# cnc3018_ctrl.net
KiCad netlist of a schematic drawn in EasyEDA
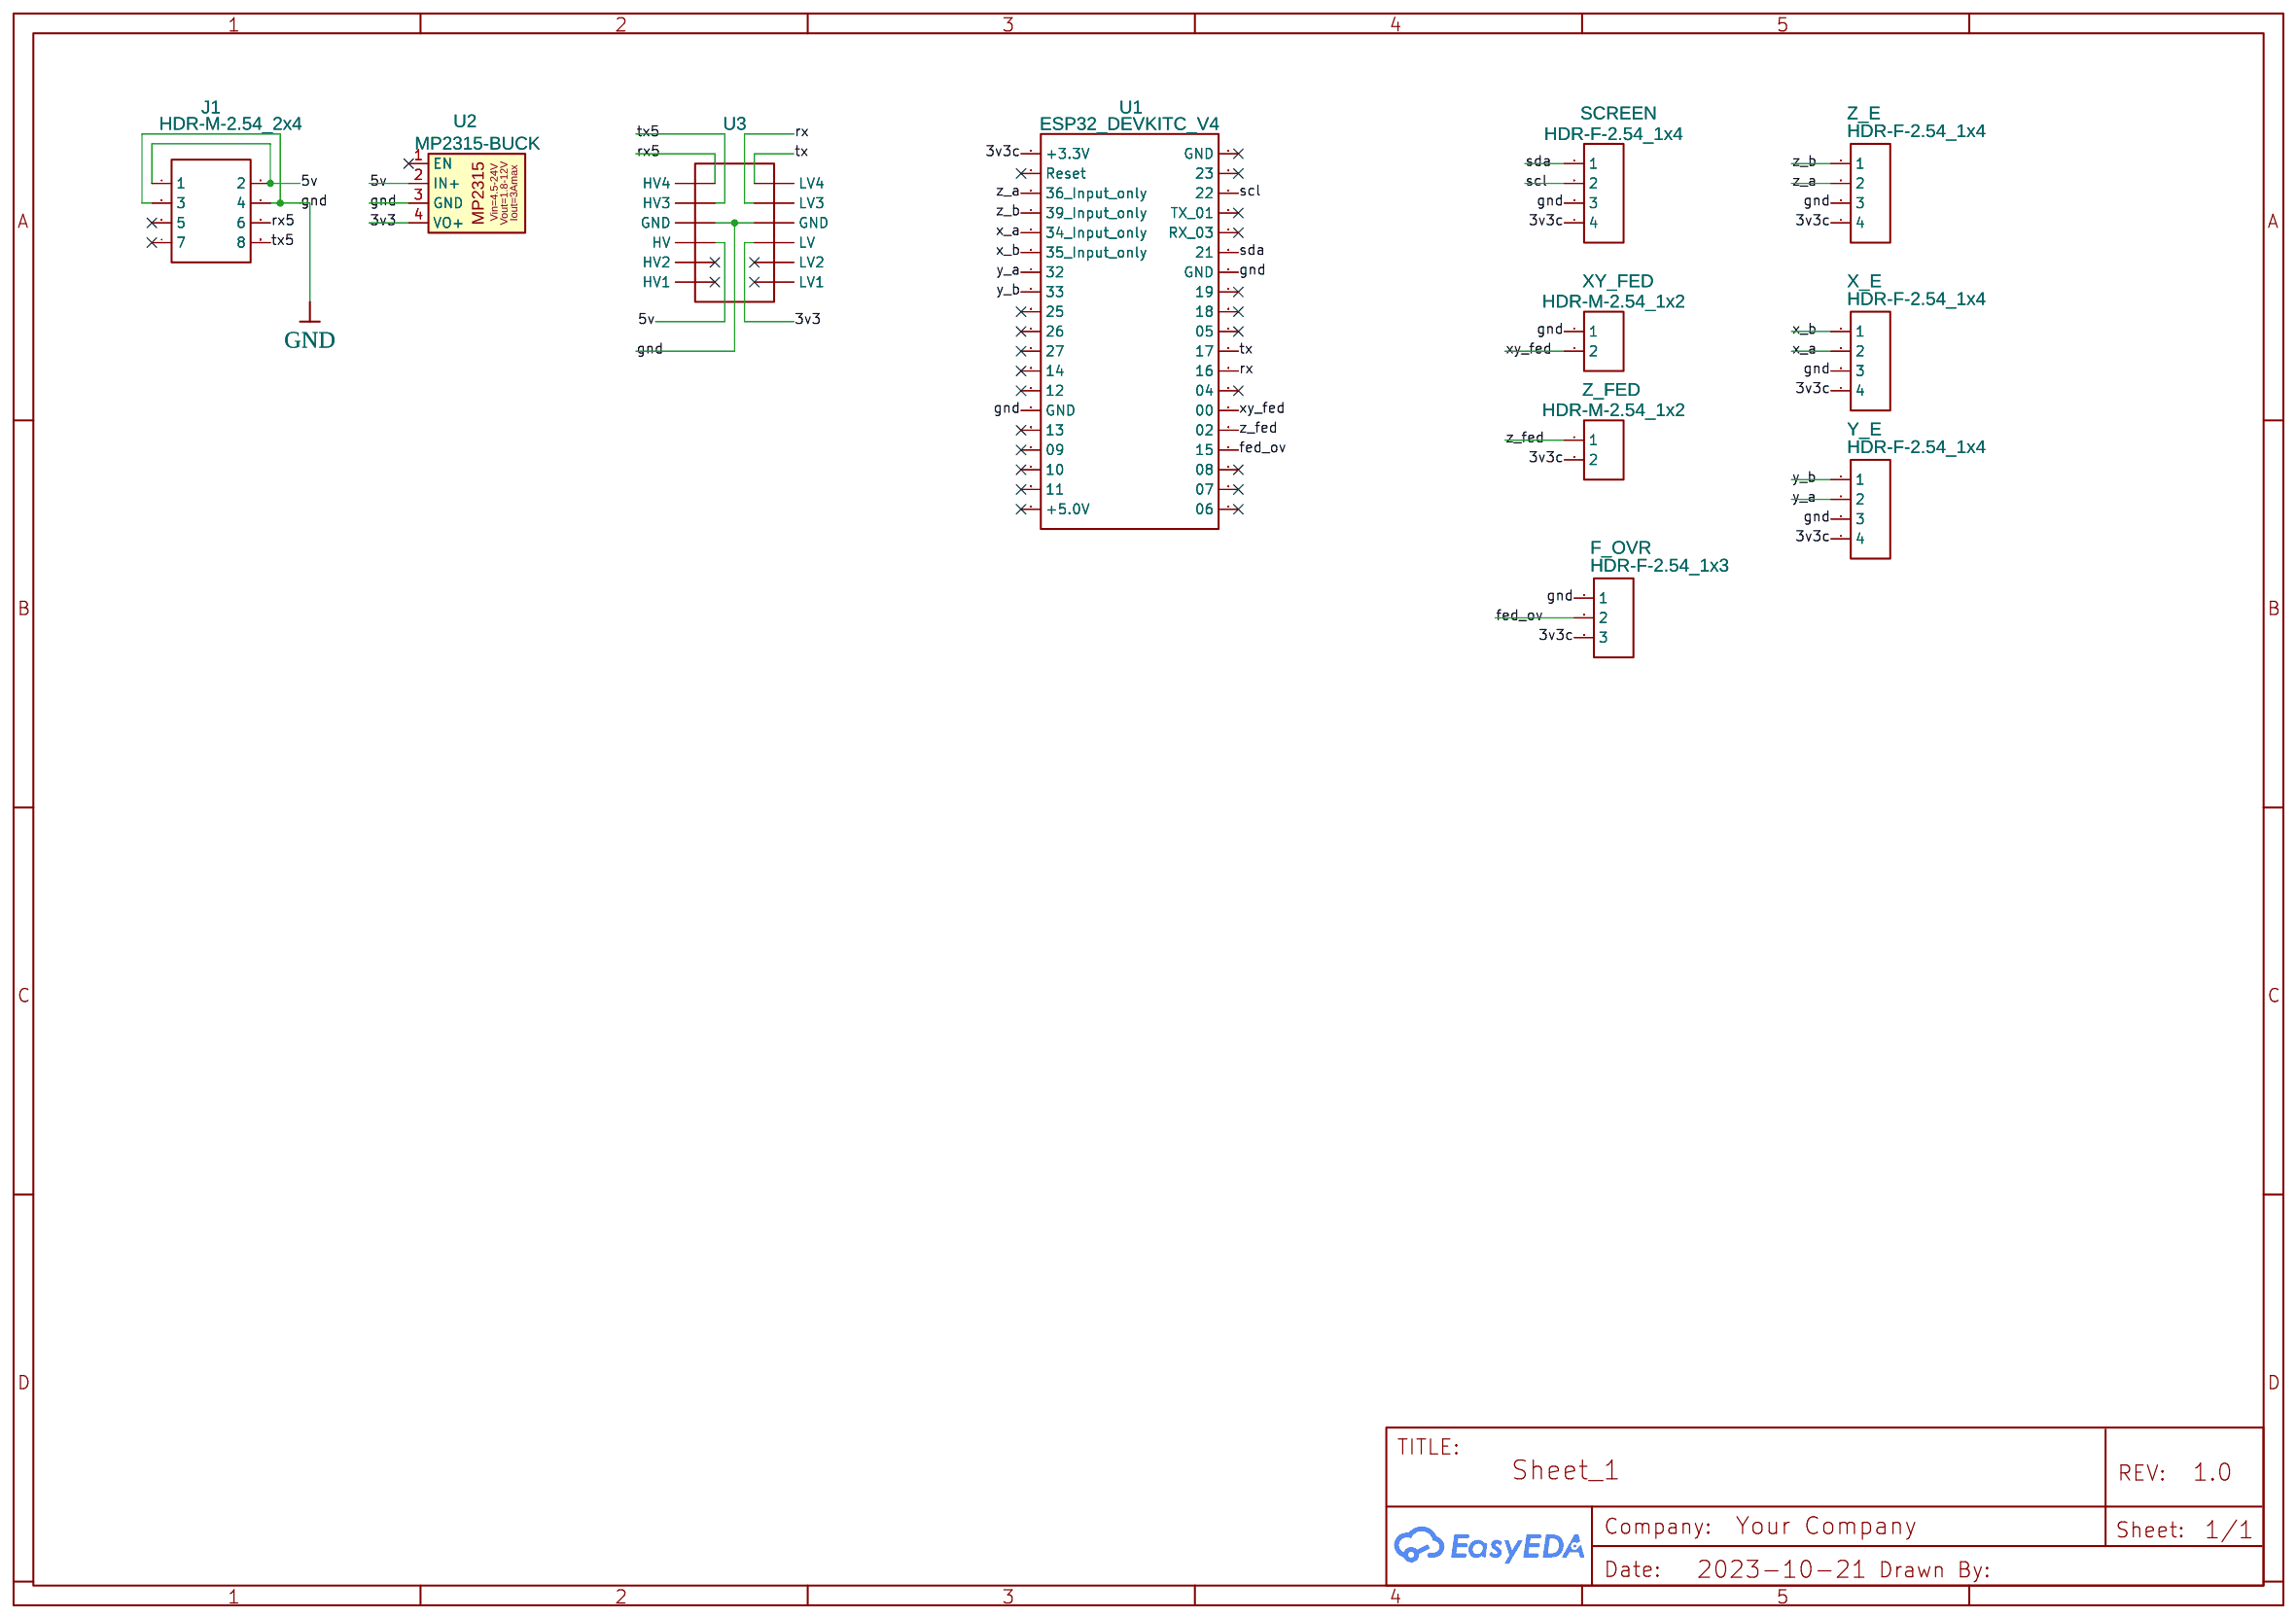
[diagram p0: schematic sheet]

(export (version "E")
  (design (tool "Eeschema 10.0.6"))
  (components
    (comp (ref "F_OVR") (value "HDR-F-2.54_1x3") (libsource (lib "") (part "HDR-F-2.54_1x3")))
    (comp (ref "J1") (value "HDR-M-2.54_2x4") (libsource (lib "") (part "HDR-M-2.54_2x4")))
    (comp (ref "SCREEN") (value "HDR-F-2.54_1x4") (libsource (lib "") (part "HDR-F-2.54_1x4")))
    (comp (ref "U1") (value "ESP32_DEVKITC_V4") (libsource (lib "") (part "ESP32_DEVKITC_V4")))
    (comp (ref "U2") (value "MP2315-BUCK") (libsource (lib "") (part "MP2315-BUCK")))
    (comp (ref "U3") (value "NO") (libsource (lib "") (part "LEVEL-CONVERTER")))
    (comp (ref "XY_FED") (value "HDR-M-2.54_1x2") (libsource (lib "") (part "HDR-M-2.54_1x2_1")))
    (comp (ref "X_E") (value "HDR-F-2.54_1x4") (libsource (lib "") (part "HDR-F-2.54_1x4_1")))
    (comp (ref "Y_E") (value "HDR-F-2.54_1x4") (libsource (lib "") (part "HDR-F-2.54_1x4_3")))
    (comp (ref "Z_E") (value "HDR-F-2.54_1x4") (libsource (lib "") (part "HDR-F-2.54_1x4_2")))
    (comp (ref "Z_FED") (value "HDR-M-2.54_1x2") (libsource (lib "") (part "HDR-M-2.54_1x2")))
  )
  (nets
    (net (code "1") (name "/3v3") (class "Default")
      (node (ref "U2") (pin "4") (pinfunction "VO+_4") (pintype "unspecified"))
      (node (ref "U3") (pin "3") (pinfunction "LV_3") (pintype "unspecified"))
    )
    (net (code "2") (name "/3v3c") (class "Default")
      (node (ref "F_OVR") (pin "3") (pinfunction "3_3") (pintype "input"))
      (node (ref "SCREEN") (pin "4") (pinfunction "4_4") (pintype "unspecified"))
      (node (ref "U1") (pin "1") (pinfunction "+3.3V_1") (pintype "unspecified"))
      (node (ref "X_E") (pin "4") (pinfunction "4_4") (pintype "unspecified"))
      (node (ref "Y_E") (pin "4") (pinfunction "4_4") (pintype "unspecified"))
      (node (ref "Z_E") (pin "4") (pinfunction "4_4") (pintype "unspecified"))
      (node (ref "Z_FED") (pin "2") (pinfunction "2_2") (pintype "unspecified"))
    )
    (net (code "3") (name "/5v") (class "Default")
      (node (ref "J1") (pin "1") (pinfunction "1_1") (pintype "unspecified"))
      (node (ref "J1") (pin "2") (pinfunction "2_2") (pintype "unspecified"))
      (node (ref "U2") (pin "2") (pinfunction "IN+_2") (pintype "unspecified"))
      (node (ref "U3") (pin "10") (pinfunction "HV_10") (pintype "unspecified"))
    )
    (net (code "4") (name "/fed_ov") (class "Default")
      (node (ref "F_OVR") (pin "2") (pinfunction "2_2") (pintype "input"))
      (node (ref "U1") (pin "23") (pinfunction "15_23") (pintype "unspecified"))
    )
    (net (code "5") (name "/rx") (class "Default")
      (node (ref "U1") (pin "27") (pinfunction "16_27") (pintype "unspecified"))
      (node (ref "U3") (pin "5") (pinfunction "LV3_5") (pintype "unspecified"))
    )
    (net (code "6") (name "/rx5") (class "Default")
      (node (ref "J1") (pin "6") (pinfunction "6_6") (pintype "unspecified"))
      (node (ref "U3") (pin "7") (pinfunction "HV4_7") (pintype "unspecified"))
    )
    (net (code "7") (name "/scl") (class "Default")
      (node (ref "SCREEN") (pin "2") (pinfunction "2_2") (pintype "unspecified"))
      (node (ref "U1") (pin "36") (pinfunction "22_36") (pintype "unspecified"))
    )
    (net (code "8") (name "/sda") (class "Default")
      (node (ref "SCREEN") (pin "1") (pinfunction "1_1") (pintype "unspecified"))
      (node (ref "U1") (pin "33") (pinfunction "21_33") (pintype "unspecified"))
    )
    (net (code "9") (name "/tx") (class "Default")
      (node (ref "U1") (pin "28") (pinfunction "17_28") (pintype "unspecified"))
      (node (ref "U3") (pin "6") (pinfunction "LV4_6") (pintype "unspecified"))
    )
    (net (code "10") (name "/tx5") (class "Default")
      (node (ref "J1") (pin "8") (pinfunction "8_8") (pintype "unspecified"))
      (node (ref "U3") (pin "8") (pinfunction "HV3_8") (pintype "unspecified"))
    )
    (net (code "11") (name "/x_a") (class "Default")
      (node (ref "U1") (pin "5") (pinfunction "34_Input_only_5") (pintype "unspecified"))
      (node (ref "X_E") (pin "2") (pinfunction "2_2") (pintype "unspecified"))
    )
    (net (code "12") (name "/x_b") (class "Default")
      (node (ref "U1") (pin "6") (pinfunction "35_Input_only_6") (pintype "unspecified"))
      (node (ref "X_E") (pin "1") (pinfunction "1_1") (pintype "unspecified"))
    )
    (net (code "13") (name "/xy_fed") (class "Default")
      (node (ref "U1") (pin "25") (pinfunction "00_25") (pintype "unspecified"))
      (node (ref "XY_FED") (pin "2") (pinfunction "2_2") (pintype "unspecified"))
    )
    (net (code "14") (name "/y_a") (class "Default")
      (node (ref "U1") (pin "7") (pinfunction "32_7") (pintype "unspecified"))
      (node (ref "Y_E") (pin "2") (pinfunction "2_2") (pintype "unspecified"))
    )
    (net (code "15") (name "/y_b") (class "Default")
      (node (ref "U1") (pin "8") (pinfunction "33_8") (pintype "unspecified"))
      (node (ref "Y_E") (pin "1") (pinfunction "1_1") (pintype "unspecified"))
    )
    (net (code "16") (name "/z_a") (class "Default")
      (node (ref "U1") (pin "3") (pinfunction "36_Input_only_3") (pintype "unspecified"))
      (node (ref "Z_E") (pin "2") (pinfunction "2_2") (pintype "unspecified"))
    )
    (net (code "17") (name "/z_b") (class "Default")
      (node (ref "U1") (pin "4") (pinfunction "39_Input_only_4") (pintype "unspecified"))
      (node (ref "Z_E") (pin "1") (pinfunction "1_1") (pintype "unspecified"))
    )
    (net (code "18") (name "/z_fed") (class "Default")
      (node (ref "U1") (pin "24") (pinfunction "02_24") (pintype "unspecified"))
      (node (ref "Z_FED") (pin "1") (pinfunction "1_1") (pintype "unspecified"))
    )
    (net (code "19") (name "GND") (class "Default")
      (node (ref "F_OVR") (pin "1") (pinfunction "1_1") (pintype "input"))
      (node (ref "J1") (pin "3") (pinfunction "3_3") (pintype "unspecified"))
      (node (ref "J1") (pin "4") (pinfunction "4_4") (pintype "unspecified"))
      (node (ref "SCREEN") (pin "3") (pinfunction "3_3") (pintype "unspecified"))
      (node (ref "U1") (pin "14") (pinfunction "GND_14") (pintype "unspecified"))
      (node (ref "U1") (pin "32") (pinfunction "GND_32") (pintype "unspecified"))
      (node (ref "U2") (pin "3") (pinfunction "GND_3") (pintype "unspecified"))
      (node (ref "U3") (pin "4") (pinfunction "GND_4") (pintype "unspecified"))
      (node (ref "U3") (pin "9") (pinfunction "GND_9") (pintype "unspecified"))
      (node (ref "XY_FED") (pin "1") (pinfunction "1_1") (pintype "unspecified"))
      (node (ref "X_E") (pin "3") (pinfunction "3_3") (pintype "unspecified"))
      (node (ref "Y_E") (pin "3") (pinfunction "3_3") (pintype "unspecified"))
      (node (ref "Z_E") (pin "3") (pinfunction "3_3") (pintype "unspecified"))
    )
    (net (code "20") (name "unconnected-(J1-Pad5)") (class "Default")
      (node (ref "J1") (pin "5") (pinfunction "5_5") (pintype "unspecified+no_connect"))
    )
    (net (code "21") (name "unconnected-(J1-Pad7)") (class "Default")
      (node (ref "J1") (pin "7") (pinfunction "7_7") (pintype "unspecified+no_connect"))
    )
    (net (code "22") (name "unconnected-(U1-+5.0V-Pad19)") (class "Default")
      (node (ref "U1") (pin "19") (pinfunction "+5.0V_19") (pintype "unspecified+no_connect"))
    )
    (net (code "23") (name "unconnected-(U1-04-Pad26)") (class "Default")
      (node (ref "U1") (pin "26") (pinfunction "04_26") (pintype "unspecified+no_connect"))
    )
    (net (code "24") (name "unconnected-(U1-05-Pad29)") (class "Default")
      (node (ref "U1") (pin "29") (pinfunction "05_29") (pintype "unspecified+no_connect"))
    )
    (net (code "25") (name "unconnected-(U1-06-Pad20)") (class "Default")
      (node (ref "U1") (pin "20") (pinfunction "06_20") (pintype "unspecified+no_connect"))
    )
    (net (code "26") (name "unconnected-(U1-07-Pad21)") (class "Default")
      (node (ref "U1") (pin "21") (pinfunction "07_21") (pintype "unspecified+no_connect"))
    )
    (net (code "27") (name "unconnected-(U1-08-Pad22)") (class "Default")
      (node (ref "U1") (pin "22") (pinfunction "08_22") (pintype "unspecified+no_connect"))
    )
    (net (code "28") (name "unconnected-(U1-09-Pad16)") (class "Default")
      (node (ref "U1") (pin "16") (pinfunction "09_16") (pintype "unspecified+no_connect"))
    )
    (net (code "29") (name "unconnected-(U1-10-Pad17)") (class "Default")
      (node (ref "U1") (pin "17") (pinfunction "10_17") (pintype "unspecified+no_connect"))
    )
    (net (code "30") (name "unconnected-(U1-11-Pad18)") (class "Default")
      (node (ref "U1") (pin "18") (pinfunction "11_18") (pintype "unspecified+no_connect"))
    )
    (net (code "31") (name "unconnected-(U1-12-Pad13)") (class "Default")
      (node (ref "U1") (pin "13") (pinfunction "12_13") (pintype "unspecified+no_connect"))
    )
    (net (code "32") (name "unconnected-(U1-13-Pad15)") (class "Default")
      (node (ref "U1") (pin "15") (pinfunction "13_15") (pintype "unspecified+no_connect"))
    )
    (net (code "33") (name "unconnected-(U1-14-Pad12)") (class "Default")
      (node (ref "U1") (pin "12") (pinfunction "14_12") (pintype "unspecified+no_connect"))
    )
    (net (code "34") (name "unconnected-(U1-18-Pad30)") (class "Default")
      (node (ref "U1") (pin "30") (pinfunction "18_30") (pintype "unspecified+no_connect"))
    )
    (net (code "35") (name "unconnected-(U1-19-Pad31)") (class "Default")
      (node (ref "U1") (pin "31") (pinfunction "19_31") (pintype "unspecified+no_connect"))
    )
    (net (code "36") (name "unconnected-(U1-23-Pad37)") (class "Default")
      (node (ref "U1") (pin "37") (pinfunction "23_37") (pintype "unspecified+no_connect"))
    )
    (net (code "37") (name "unconnected-(U1-25-Pad9)") (class "Default")
      (node (ref "U1") (pin "9") (pinfunction "25_9") (pintype "unspecified+no_connect"))
    )
    (net (code "38") (name "unconnected-(U1-26-Pad10)") (class "Default")
      (node (ref "U1") (pin "10") (pinfunction "26_10") (pintype "unspecified+no_connect"))
    )
    (net (code "39") (name "unconnected-(U1-27-Pad11)") (class "Default")
      (node (ref "U1") (pin "11") (pinfunction "27_11") (pintype "unspecified+no_connect"))
    )
    (net (code "40") (name "unconnected-(U1-GND-Pad38)") (class "Default")
      (node (ref "U1") (pin "38") (pinfunction "GND_38") (pintype "unspecified+no_connect"))
    )
    (net (code "41") (name "unconnected-(U1-RX_03-Pad34)") (class "Default")
      (node (ref "U1") (pin "34") (pinfunction "RX_03_34") (pintype "unspecified+no_connect"))
    )
    (net (code "42") (name "unconnected-(U1-Reset-Pad2)") (class "Default")
      (node (ref "U1") (pin "2") (pinfunction "Reset_2") (pintype "unspecified+no_connect"))
    )
    (net (code "43") (name "unconnected-(U1-TX_01-Pad35)") (class "Default")
      (node (ref "U1") (pin "35") (pinfunction "TX_01_35") (pintype "unspecified+no_connect"))
    )
    (net (code "44") (name "unconnected-(U2-EN-Pad1)") (class "Default")
      (node (ref "U2") (pin "1") (pinfunction "EN_1") (pintype "unspecified+no_connect"))
    )
    (net (code "45") (name "unconnected-(U3-HV1-Pad12)") (class "Default")
      (node (ref "U3") (pin "12") (pinfunction "HV1_12") (pintype "unspecified+no_connect"))
    )
    (net (code "46") (name "unconnected-(U3-HV2-Pad11)") (class "Default")
      (node (ref "U3") (pin "11") (pinfunction "HV2_11") (pintype "unspecified+no_connect"))
    )
    (net (code "47") (name "unconnected-(U3-LV1-Pad1)") (class "Default")
      (node (ref "U3") (pin "1") (pinfunction "LV1_1") (pintype "unspecified+no_connect"))
    )
    (net (code "48") (name "unconnected-(U3-LV2-Pad2)") (class "Default")
      (node (ref "U3") (pin "2") (pinfunction "LV2_2") (pintype "unspecified+no_connect"))
    )
  )
)
